# UCirKitUserStudy1.net
KiCad netlist of a schematic drawn in EAGLE
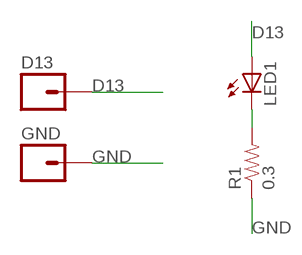
[diagram p0: schematic, sheet 1]

(export (version "E")
  (design (tool "Eeschema 10.0.6"))
  (components
    (comp (ref "D13")
      (value "M01PTH")
      (footprint "eagle-import:1X01")
      (libsource (lib "eagle-import") (part "M01PTH"))
    )
    (comp (ref "GND")
      (value "M01PTH")
      (footprint "eagle-import:1X01")
      (libsource (lib "eagle-import") (part "M01PTH"))
    )
    (comp (ref "LED1")
      (value "LEDCHIPLED_0805")
      (footprint "eagle-import:CHIPLED_0805")
      (libsource (lib "eagle-import") (part "LEDCHIPLED_0805"))
    )
    (comp (ref "R1")
      (value "0.3")
      (footprint "eagle-import:0805")
      (libsource (lib "eagle-import") (part "0.3OHM-1/8W-1%(0805)"))
    )
  )
  (nets
    (net (code "1") (name "/D13") (class "Default")
      (node (ref "D13") (pin "1") (pinfunction "1_1") (pintype "passive"))
      (node (ref "LED1") (pin "A") (pinfunction "A_A") (pintype "passive"))
    )
    (net (code "2") (name "/GND") (class "Default")
      (node (ref "GND") (pin "1") (pinfunction "1_1") (pintype "passive"))
      (node (ref "R1") (pin "1") (pinfunction "1_1") (pintype "passive"))
    )
    (net (code "3") (name "Net-(LED1-PadC)") (class "Default")
      (node (ref "LED1") (pin "C") (pinfunction "C_C") (pintype "passive"))
      (node (ref "R1") (pin "2") (pinfunction "2_2") (pintype "passive"))
    )
  )
)
